# PiHAT_Power.net
KiCad netlist of a schematic drawn in Altium Designer
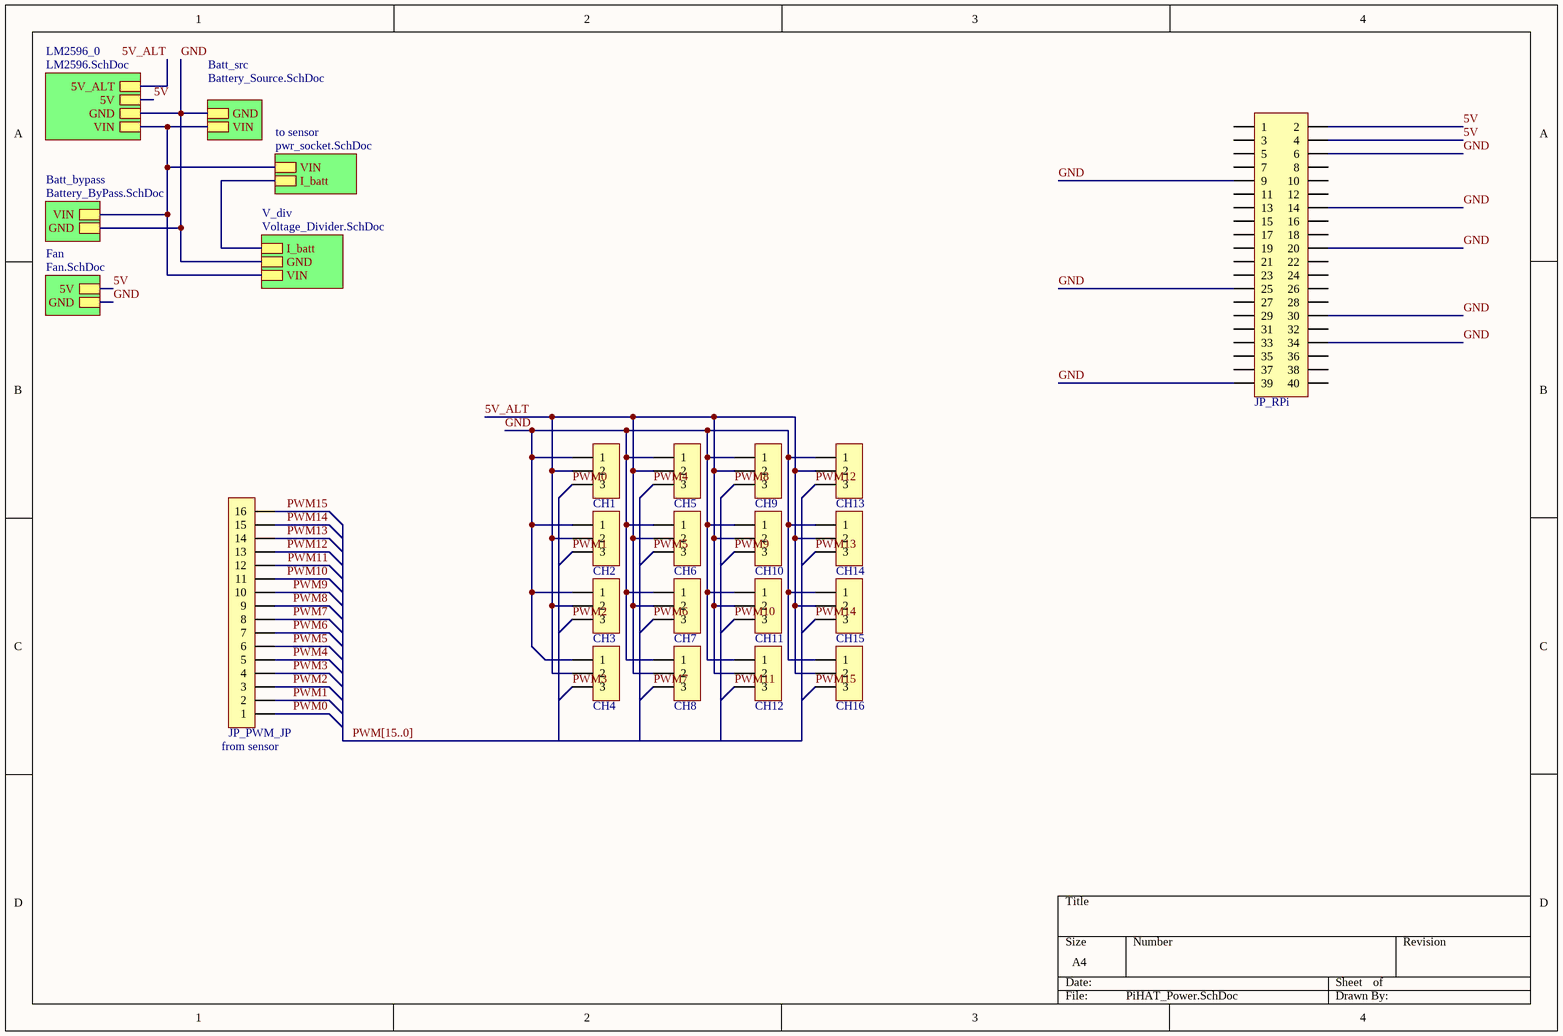
[diagram p0: PiHAT_Power.SchDoc]

(export (version "E")
  (design (tool "Eeschema 10.0.6"))
  (components
    (comp (ref "CH1")
      (value "HDR-1X3")
      (footprint "HDR2.54-LI-3P")
      (description "3P接插件")
      (fields (field (name "版权归属") "源创客"))
      (libsource (lib "4.6   - 接插件-脚距2.54") (part "Header 3"))
    )
    (comp (ref "CH2")
      (value "HDR-1X3")
      (footprint "HDR2.54-LI-3P")
      (description "3P接插件")
      (fields (field (name "版权归属") "源创客"))
      (libsource (lib "4.6   - 接插件-脚距2.54") (part "Header 3"))
    )
    (comp (ref "CH3")
      (value "HDR-1X3")
      (footprint "HDR2.54-LI-3P")
      (description "3P接插件")
      (fields (field (name "版权归属") "源创客"))
      (libsource (lib "4.6   - 接插件-脚距2.54") (part "Header 3"))
    )
    (comp (ref "CH4")
      (value "HDR-1X3")
      (footprint "HDR2.54-LI-3P")
      (description "3P接插件")
      (fields (field (name "版权归属") "源创客"))
      (libsource (lib "4.6   - 接插件-脚距2.54") (part "Header 3"))
    )
    (comp (ref "CH5")
      (value "HDR-1X3")
      (footprint "HDR2.54-LI-3P")
      (description "3P接插件")
      (fields (field (name "版权归属") "源创客"))
      (libsource (lib "4.6   - 接插件-脚距2.54") (part "Header 3"))
    )
    (comp (ref "CH6")
      (value "HDR-1X3")
      (footprint "HDR2.54-LI-3P")
      (description "3P接插件")
      (fields (field (name "版权归属") "源创客"))
      (libsource (lib "4.6   - 接插件-脚距2.54") (part "Header 3"))
    )
    (comp (ref "CH7")
      (value "HDR-1X3")
      (footprint "HDR2.54-LI-3P")
      (description "3P接插件")
      (fields (field (name "版权归属") "源创客"))
      (libsource (lib "4.6   - 接插件-脚距2.54") (part "Header 3"))
    )
    (comp (ref "CH8")
      (value "HDR-1X3")
      (footprint "HDR2.54-LI-3P")
      (description "3P接插件")
      (fields (field (name "版权归属") "源创客"))
      (libsource (lib "4.6   - 接插件-脚距2.54") (part "Header 3"))
    )
    (comp (ref "CH9")
      (value "HDR-1X3")
      (footprint "HDR2.54-LI-3P")
      (description "3P接插件")
      (fields (field (name "版权归属") "源创客"))
      (libsource (lib "4.6   - 接插件-脚距2.54") (part "Header 3"))
    )
    (comp (ref "CH10")
      (value "HDR-1X3")
      (footprint "HDR2.54-LI-3P")
      (description "3P接插件")
      (fields (field (name "版权归属") "源创客"))
      (libsource (lib "4.6   - 接插件-脚距2.54") (part "Header 3"))
    )
    (comp (ref "CH11")
      (value "HDR-1X3")
      (footprint "HDR2.54-LI-3P")
      (description "3P接插件")
      (fields (field (name "版权归属") "源创客"))
      (libsource (lib "4.6   - 接插件-脚距2.54") (part "Header 3"))
    )
    (comp (ref "CH12")
      (value "HDR-1X3")
      (footprint "HDR2.54-LI-3P")
      (description "3P接插件")
      (fields (field (name "版权归属") "源创客"))
      (libsource (lib "4.6   - 接插件-脚距2.54") (part "Header 3"))
    )
    (comp (ref "CH13")
      (value "HDR-1X3")
      (footprint "HDR2.54-LI-3P")
      (description "3P接插件")
      (fields (field (name "版权归属") "源创客"))
      (libsource (lib "4.6   - 接插件-脚距2.54") (part "Header 3"))
    )
    (comp (ref "CH14")
      (value "HDR-1X3")
      (footprint "HDR2.54-LI-3P")
      (description "3P接插件")
      (fields (field (name "版权归属") "源创客"))
      (libsource (lib "4.6   - 接插件-脚距2.54") (part "Header 3"))
    )
    (comp (ref "CH15")
      (value "HDR-1X3")
      (footprint "HDR2.54-LI-3P")
      (description "3P接插件")
      (fields (field (name "版权归属") "源创客"))
      (libsource (lib "4.6   - 接插件-脚距2.54") (part "Header 3"))
    )
    (comp (ref "CH16")
      (value "HDR-1X3")
      (footprint "HDR2.54-LI-3P")
      (description "3P接插件")
      (fields (field (name "版权归属") "源创客"))
      (libsource (lib "4.6   - 接插件-脚距2.54") (part "Header 3"))
    )
    (comp (ref "JP_PWM_JP")
      (value "HDR-1X16")
      (footprint "HDR2.54-M-LI-16P")
      (description "16P接插件")
      (fields (field (name "版权归属") "源创客"))
      (libsource (lib "4.5   - 接插件-脚距2.54") (part "Header 16"))
    )
    (comp (ref "JP_RPi")
      (value "Header 2X11")
      (footprint "HDR2.54-LI-2x20P")
      (description "20*2P接插件")
      (fields (field (name "版权归属") "源创客"))
      (libsource (lib "4.5   - 接插件-脚距2.54") (part "Header 20X2"))
    )
  )
  (nets
    (net (code "1") (name "/5V") (class "Default")
      (node (ref "JP_RPi") (pin "2") (pinfunction "2_2") (pintype "passive"))
      (node (ref "JP_RPi") (pin "4") (pinfunction "4_4") (pintype "passive"))
    )
    (net (code "2") (name "/5V_ALT") (class "Default")
      (node (ref "CH1") (pin "2") (pinfunction "2_2") (pintype "passive"))
      (node (ref "CH10") (pin "2") (pinfunction "2_2") (pintype "passive"))
      (node (ref "CH11") (pin "2") (pinfunction "2_2") (pintype "passive"))
      (node (ref "CH12") (pin "2") (pinfunction "2_2") (pintype "passive"))
      (node (ref "CH13") (pin "2") (pinfunction "2_2") (pintype "passive"))
      (node (ref "CH14") (pin "2") (pinfunction "2_2") (pintype "passive"))
      (node (ref "CH15") (pin "2") (pinfunction "2_2") (pintype "passive"))
      (node (ref "CH16") (pin "2") (pinfunction "2_2") (pintype "passive"))
      (node (ref "CH2") (pin "2") (pinfunction "2_2") (pintype "passive"))
      (node (ref "CH3") (pin "2") (pinfunction "2_2") (pintype "passive"))
      (node (ref "CH4") (pin "2") (pinfunction "2_2") (pintype "passive"))
      (node (ref "CH5") (pin "2") (pinfunction "2_2") (pintype "passive"))
      (node (ref "CH6") (pin "2") (pinfunction "2_2") (pintype "passive"))
      (node (ref "CH7") (pin "2") (pinfunction "2_2") (pintype "passive"))
      (node (ref "CH8") (pin "2") (pinfunction "2_2") (pintype "passive"))
      (node (ref "CH9") (pin "2") (pinfunction "2_2") (pintype "passive"))
    )
    (net (code "3") (name "/GND") (class "Default")
      (node (ref "CH1") (pin "1") (pinfunction "1_1") (pintype "passive"))
      (node (ref "CH10") (pin "1") (pinfunction "1_1") (pintype "passive"))
      (node (ref "CH11") (pin "1") (pinfunction "1_1") (pintype "passive"))
      (node (ref "CH12") (pin "1") (pinfunction "1_1") (pintype "passive"))
      (node (ref "CH13") (pin "1") (pinfunction "1_1") (pintype "passive"))
      (node (ref "CH14") (pin "1") (pinfunction "1_1") (pintype "passive"))
      (node (ref "CH15") (pin "1") (pinfunction "1_1") (pintype "passive"))
      (node (ref "CH16") (pin "1") (pinfunction "1_1") (pintype "passive"))
      (node (ref "CH2") (pin "1") (pinfunction "1_1") (pintype "passive"))
      (node (ref "CH3") (pin "1") (pinfunction "1_1") (pintype "passive"))
      (node (ref "CH4") (pin "1") (pinfunction "1_1") (pintype "passive"))
      (node (ref "CH5") (pin "1") (pinfunction "1_1") (pintype "passive"))
      (node (ref "CH6") (pin "1") (pinfunction "1_1") (pintype "passive"))
      (node (ref "CH7") (pin "1") (pinfunction "1_1") (pintype "passive"))
      (node (ref "CH8") (pin "1") (pinfunction "1_1") (pintype "passive"))
      (node (ref "CH9") (pin "1") (pinfunction "1_1") (pintype "passive"))
      (node (ref "JP_RPi") (pin "14") (pinfunction "14_14") (pintype "passive"))
      (node (ref "JP_RPi") (pin "20") (pinfunction "20_20") (pintype "passive"))
      (node (ref "JP_RPi") (pin "25") (pinfunction "25_25") (pintype "passive"))
      (node (ref "JP_RPi") (pin "30") (pinfunction "30_30") (pintype "passive"))
      (node (ref "JP_RPi") (pin "34") (pinfunction "34_34") (pintype "passive"))
      (node (ref "JP_RPi") (pin "39") (pinfunction "39_39") (pintype "passive"))
      (node (ref "JP_RPi") (pin "6") (pinfunction "6_6") (pintype "passive"))
      (node (ref "JP_RPi") (pin "9") (pinfunction "9_9") (pintype "passive"))
    )
    (net (code "5") (name "/PWM0") (class "Default")
      (node (ref "CH1") (pin "3") (pinfunction "3_3") (pintype "passive"))
      (node (ref "JP_PWM_JP") (pin "1") (pinfunction "1_1") (pintype "passive"))
    )
    (net (code "6") (name "/PWM1") (class "Default")
      (node (ref "CH2") (pin "3") (pinfunction "3_3") (pintype "passive"))
      (node (ref "JP_PWM_JP") (pin "2") (pinfunction "2_2") (pintype "passive"))
    )
    (net (code "7") (name "/PWM2") (class "Default")
      (node (ref "CH3") (pin "3") (pinfunction "3_3") (pintype "passive"))
      (node (ref "JP_PWM_JP") (pin "3") (pinfunction "3_3") (pintype "passive"))
    )
    (net (code "8") (name "/PWM3") (class "Default")
      (node (ref "CH4") (pin "3") (pinfunction "3_3") (pintype "passive"))
      (node (ref "JP_PWM_JP") (pin "4") (pinfunction "4_4") (pintype "passive"))
    )
    (net (code "9") (name "/PWM4") (class "Default")
      (node (ref "CH5") (pin "3") (pinfunction "3_3") (pintype "passive"))
      (node (ref "JP_PWM_JP") (pin "5") (pinfunction "5_5") (pintype "passive"))
    )
    (net (code "10") (name "/PWM5") (class "Default")
      (node (ref "CH6") (pin "3") (pinfunction "3_3") (pintype "passive"))
      (node (ref "JP_PWM_JP") (pin "6") (pinfunction "6_6") (pintype "passive"))
    )
    (net (code "11") (name "/PWM6") (class "Default")
      (node (ref "CH7") (pin "3") (pinfunction "3_3") (pintype "passive"))
      (node (ref "JP_PWM_JP") (pin "7") (pinfunction "7_7") (pintype "passive"))
    )
    (net (code "12") (name "/PWM7") (class "Default")
      (node (ref "CH8") (pin "3") (pinfunction "3_3") (pintype "passive"))
      (node (ref "JP_PWM_JP") (pin "8") (pinfunction "8_8") (pintype "passive"))
    )
    (net (code "13") (name "/PWM8") (class "Default")
      (node (ref "CH9") (pin "3") (pinfunction "3_3") (pintype "passive"))
      (node (ref "JP_PWM_JP") (pin "9") (pinfunction "9_9") (pintype "passive"))
    )
    (net (code "14") (name "/PWM9") (class "Default")
      (node (ref "CH10") (pin "3") (pinfunction "3_3") (pintype "passive"))
      (node (ref "JP_PWM_JP") (pin "10") (pinfunction "10_10") (pintype "passive"))
    )
    (net (code "15") (name "/PWM10") (class "Default")
      (node (ref "CH11") (pin "3") (pinfunction "3_3") (pintype "passive"))
      (node (ref "JP_PWM_JP") (pin "11") (pinfunction "11_11") (pintype "passive"))
    )
    (net (code "16") (name "/PWM11") (class "Default")
      (node (ref "CH12") (pin "3") (pinfunction "3_3") (pintype "passive"))
      (node (ref "JP_PWM_JP") (pin "12") (pinfunction "12_12") (pintype "passive"))
    )
    (net (code "17") (name "/PWM12") (class "Default")
      (node (ref "CH13") (pin "3") (pinfunction "3_3") (pintype "passive"))
      (node (ref "JP_PWM_JP") (pin "13") (pinfunction "13_13") (pintype "passive"))
    )
    (net (code "18") (name "/PWM13") (class "Default")
      (node (ref "CH14") (pin "3") (pinfunction "3_3") (pintype "passive"))
      (node (ref "JP_PWM_JP") (pin "14") (pinfunction "14_14") (pintype "passive"))
    )
    (net (code "19") (name "/PWM14") (class "Default")
      (node (ref "CH15") (pin "3") (pinfunction "3_3") (pintype "passive"))
      (node (ref "JP_PWM_JP") (pin "15") (pinfunction "15_15") (pintype "passive"))
    )
    (net (code "20") (name "/PWM15") (class "Default")
      (node (ref "CH16") (pin "3") (pinfunction "3_3") (pintype "passive"))
      (node (ref "JP_PWM_JP") (pin "16") (pinfunction "16_16") (pintype "passive"))
    )
    (net (code "23") (name "unconnected-(JP_RPi-Pad1)") (class "Default")
      (node (ref "JP_RPi") (pin "1") (pinfunction "1_1") (pintype "passive"))
    )
    (net (code "24") (name "unconnected-(JP_RPi-Pad3)") (class "Default")
      (node (ref "JP_RPi") (pin "3") (pinfunction "3_3") (pintype "passive"))
    )
    (net (code "25") (name "unconnected-(JP_RPi-Pad5)") (class "Default")
      (node (ref "JP_RPi") (pin "5") (pinfunction "5_5") (pintype "passive"))
    )
    (net (code "26") (name "unconnected-(JP_RPi-Pad7)") (class "Default")
      (node (ref "JP_RPi") (pin "7") (pinfunction "7_7") (pintype "passive"))
    )
    (net (code "27") (name "unconnected-(JP_RPi-Pad8)") (class "Default")
      (node (ref "JP_RPi") (pin "8") (pinfunction "8_8") (pintype "passive"))
    )
    (net (code "28") (name "unconnected-(JP_RPi-Pad10)") (class "Default")
      (node (ref "JP_RPi") (pin "10") (pinfunction "10_10") (pintype "passive"))
    )
    (net (code "29") (name "unconnected-(JP_RPi-Pad11)") (class "Default")
      (node (ref "JP_RPi") (pin "11") (pinfunction "11_11") (pintype "passive"))
    )
    (net (code "30") (name "unconnected-(JP_RPi-Pad12)") (class "Default")
      (node (ref "JP_RPi") (pin "12") (pinfunction "12_12") (pintype "passive"))
    )
    (net (code "31") (name "unconnected-(JP_RPi-Pad13)") (class "Default")
      (node (ref "JP_RPi") (pin "13") (pinfunction "13_13") (pintype "passive"))
    )
    (net (code "32") (name "unconnected-(JP_RPi-Pad15)") (class "Default")
      (node (ref "JP_RPi") (pin "15") (pinfunction "15_15") (pintype "passive"))
    )
    (net (code "33") (name "unconnected-(JP_RPi-Pad16)") (class "Default")
      (node (ref "JP_RPi") (pin "16") (pinfunction "16_16") (pintype "passive"))
    )
    (net (code "34") (name "unconnected-(JP_RPi-Pad17)") (class "Default")
      (node (ref "JP_RPi") (pin "17") (pinfunction "17_17") (pintype "passive"))
    )
    (net (code "35") (name "unconnected-(JP_RPi-Pad18)") (class "Default")
      (node (ref "JP_RPi") (pin "18") (pinfunction "18_18") (pintype "passive"))
    )
    (net (code "36") (name "unconnected-(JP_RPi-Pad19)") (class "Default")
      (node (ref "JP_RPi") (pin "19") (pinfunction "19_19") (pintype "passive"))
    )
    (net (code "37") (name "unconnected-(JP_RPi-Pad21)") (class "Default")
      (node (ref "JP_RPi") (pin "21") (pinfunction "21_21") (pintype "passive"))
    )
    (net (code "38") (name "unconnected-(JP_RPi-Pad22)") (class "Default")
      (node (ref "JP_RPi") (pin "22") (pinfunction "22_22") (pintype "passive"))
    )
    (net (code "39") (name "unconnected-(JP_RPi-Pad23)") (class "Default")
      (node (ref "JP_RPi") (pin "23") (pinfunction "23_23") (pintype "passive"))
    )
    (net (code "40") (name "unconnected-(JP_RPi-Pad24)") (class "Default")
      (node (ref "JP_RPi") (pin "24") (pinfunction "24_24") (pintype "passive"))
    )
    (net (code "41") (name "unconnected-(JP_RPi-Pad26)") (class "Default")
      (node (ref "JP_RPi") (pin "26") (pinfunction "26_26") (pintype "passive"))
    )
    (net (code "42") (name "unconnected-(JP_RPi-Pad27)") (class "Default")
      (node (ref "JP_RPi") (pin "27") (pinfunction "27_27") (pintype "passive"))
    )
    (net (code "43") (name "unconnected-(JP_RPi-Pad28)") (class "Default")
      (node (ref "JP_RPi") (pin "28") (pinfunction "28_28") (pintype "passive"))
    )
    (net (code "44") (name "unconnected-(JP_RPi-Pad29)") (class "Default")
      (node (ref "JP_RPi") (pin "29") (pinfunction "29_29") (pintype "passive"))
    )
    (net (code "45") (name "unconnected-(JP_RPi-Pad31)") (class "Default")
      (node (ref "JP_RPi") (pin "31") (pinfunction "31_31") (pintype "passive"))
    )
    (net (code "46") (name "unconnected-(JP_RPi-Pad32)") (class "Default")
      (node (ref "JP_RPi") (pin "32") (pinfunction "32_32") (pintype "passive"))
    )
    (net (code "47") (name "unconnected-(JP_RPi-Pad33)") (class "Default")
      (node (ref "JP_RPi") (pin "33") (pinfunction "33_33") (pintype "passive"))
    )
    (net (code "48") (name "unconnected-(JP_RPi-Pad35)") (class "Default")
      (node (ref "JP_RPi") (pin "35") (pinfunction "35_35") (pintype "passive"))
    )
    (net (code "49") (name "unconnected-(JP_RPi-Pad36)") (class "Default")
      (node (ref "JP_RPi") (pin "36") (pinfunction "36_36") (pintype "passive"))
    )
    (net (code "50") (name "unconnected-(JP_RPi-Pad37)") (class "Default")
      (node (ref "JP_RPi") (pin "37") (pinfunction "37_37") (pintype "passive"))
    )
    (net (code "51") (name "unconnected-(JP_RPi-Pad38)") (class "Default")
      (node (ref "JP_RPi") (pin "38") (pinfunction "38_38") (pintype "passive"))
    )
    (net (code "52") (name "unconnected-(JP_RPi-Pad40)") (class "Default")
      (node (ref "JP_RPi") (pin "40") (pinfunction "40_40") (pintype "passive"))
    )
  )
)
